# Mach_PLC.net
KiCad netlist of a schematic drawn in Altium Designer
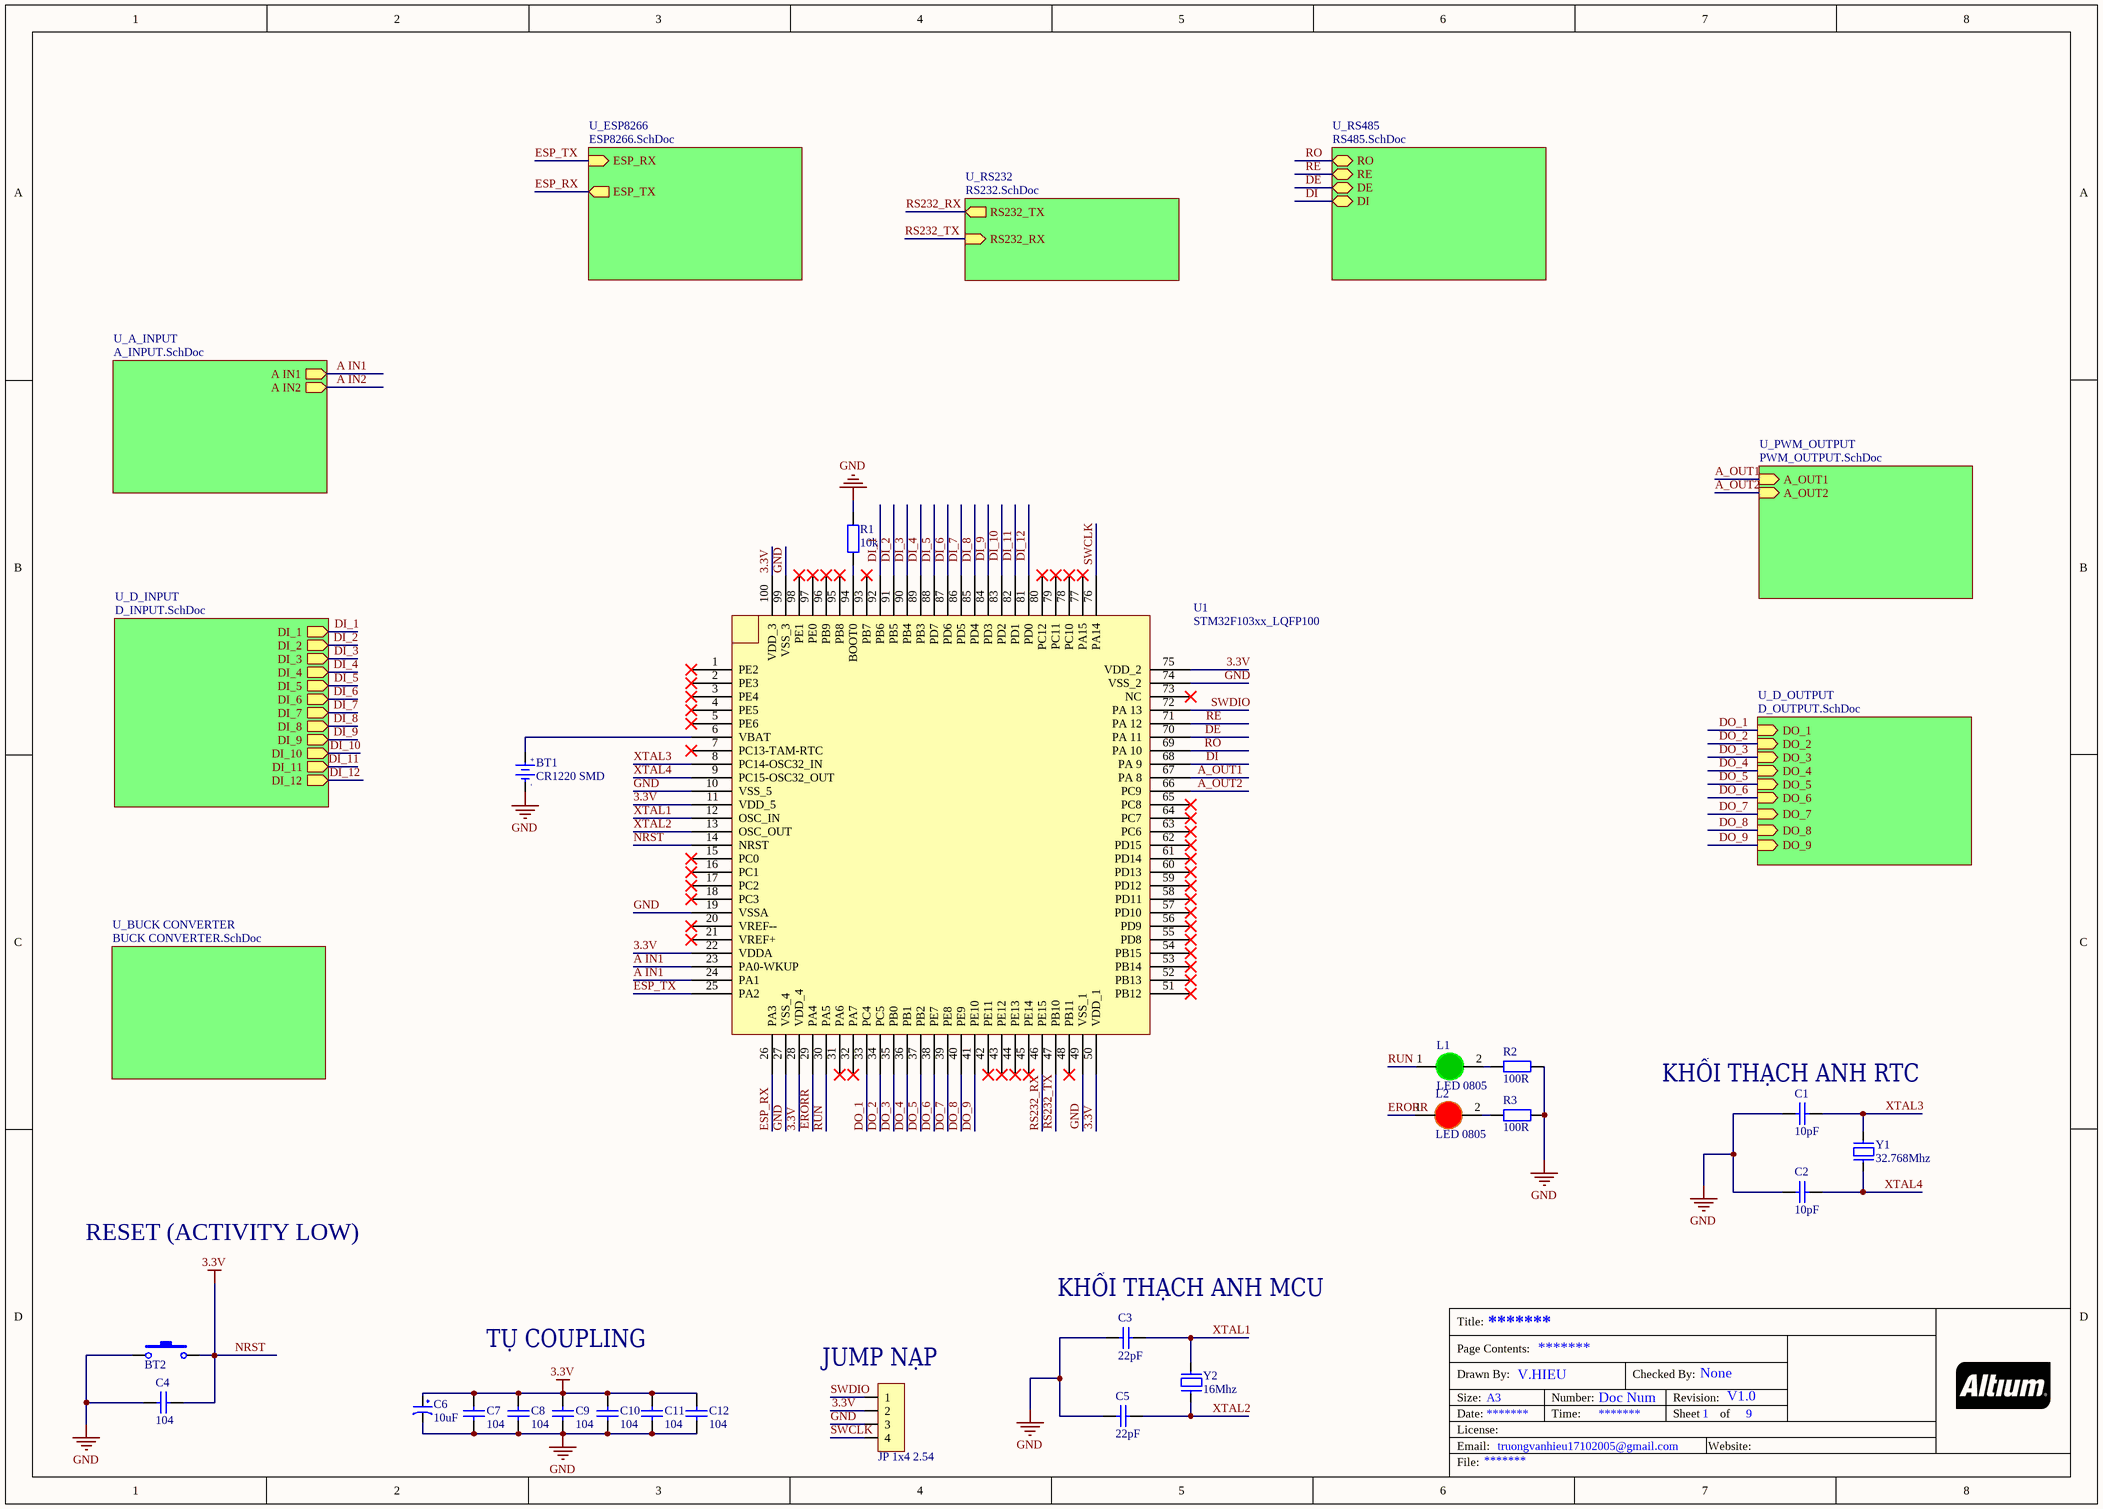
[diagram p0: Mach_PLC.SchDoc]

(export (version "E")
  (design (tool "Eeschema 10.0.6"))
  (components
    (comp (ref "BT1")
      (value "CR1220 SMD")
      (footprint "DE PIN CR1220")
      (libsource (lib "Altium_Lib_by_KhueNguyenCreator") (part "De pin CR1220 SMD"))
    )
    (comp (ref "BT2")
      (value "Nut Nhan 2 Chan SMD 3x6x2.5")
      (footprint "Nut Nhan 2 Chan SMD 3x6x2.5")
      (libsource (lib "Altium_Lib_by_KhueNguyenCreator") (part "Nut Nhan 2 Chan SMD 3x6x2.5"))
    )
    (comp (ref "C1")
      (value "10pF")
      (footprint "tu 0805")
      (description "Dán")
      (libsource (lib "Altium_Lib_by_KhueNguyenCreator") (part "Tu 0805 10pF 50V 10%"))
    )
    (comp (ref "C2")
      (value "10pF")
      (footprint "tu 0805")
      (description "Dán")
      (libsource (lib "Altium_Lib_by_KhueNguyenCreator") (part "Tu 0805 10pF 50V 10%"))
    )
    (comp (ref "C3")
      (value "22pF")
      (footprint "tu 0805")
      (description "Dán")
      (libsource (lib "Altium_Lib_by_KhueNguyenCreator") (part "Tu 0805 22pF 50V 10%"))
    )
    (comp (ref "C4")
      (value "104")
      (footprint "tu 0805")
      (description "Dán")
      (libsource (lib "Altium_Lib_by_KhueNguyenCreator") (part "Tu 0805 104 50V 10%"))
    )
    (comp (ref "C5")
      (value "22pF")
      (footprint "tu 0805")
      (description "Dán")
      (libsource (lib "Altium_Lib_by_KhueNguyenCreator") (part "Tu 0805 22pF 50V 10%"))
    )
    (comp (ref "C6")
      (value "10uF")
      (footprint "tu tantalum smd3216")
      (description "Dán")
      (libsource (lib "Altium_Lib_by_KhueNguyenCreator") (part "Tu tantalum 10uF 16V SMD3216"))
    )
    (comp (ref "C7")
      (value "104")
      (footprint "tu 0805")
      (description "Dán")
      (libsource (lib "Altium_Lib_by_KhueNguyenCreator") (part "Tu 0805 104 50V 10%"))
    )
    (comp (ref "C8")
      (value "104")
      (footprint "tu 0805")
      (description "Dán")
      (libsource (lib "Altium_Lib_by_KhueNguyenCreator") (part "Tu 0805 104 50V 10%"))
    )
    (comp (ref "C9")
      (value "104")
      (footprint "tu 0805")
      (description "Dán")
      (libsource (lib "Altium_Lib_by_KhueNguyenCreator") (part "Tu 0805 104 50V 10%"))
    )
    (comp (ref "C10")
      (value "104")
      (footprint "tu 0805")
      (description "Dán")
      (libsource (lib "Altium_Lib_by_KhueNguyenCreator") (part "Tu 0805 104 50V 10%"))
    )
    (comp (ref "C11")
      (value "104")
      (footprint "tu 0805")
      (description "Dán")
      (libsource (lib "Altium_Lib_by_KhueNguyenCreator") (part "Tu 0805 104 50V 10%"))
    )
    (comp (ref "C12")
      (value "104")
      (footprint "tu 0805")
      (description "Dán")
      (libsource (lib "Altium_Lib_by_KhueNguyenCreator") (part "Tu 0805 104 50V 10%"))
    )
    (comp (ref "JP1")
      (value "JP 1x4 2.54")
      (footprint "JP 1x4 DT")
      (description "Cắm")
      (libsource (lib "Altium_Lib_by_KhueNguyenCreator") (part "JP 1x4 2.54 Duc Thang"))
    )
    (comp (ref "L1")
      (value "LED 0805")
      (footprint "LED-0805-Green")
      (description "Dán")
      (libsource (lib "Altium_Lib_by_KhueNguyenCreator") (part "LED 0805 Xanh La"))
    )
    (comp (ref "L2")
      (value "LED 0805")
      (footprint "LED-0805-Red")
      (description "Dán")
      (libsource (lib "Altium_Lib_by_KhueNguyenCreator") (part "LED 0805 Do"))
    )
    (comp (ref "R1")
      (value "10k")
      (footprint "tro smd 0805")
      (description "Dán")
      (libsource (lib "Altium_Lib_by_KhueNguyenCreator") (part "Tro 0805 1% 10k"))
    )
    (comp (ref "R2")
      (value "100R")
      (footprint "tro smd 0805")
      (description "Dán")
      (libsource (lib "Altium_Lib_by_KhueNguyenCreator") (part "Tro 0805 5% 100R"))
    )
    (comp (ref "R3")
      (value "100R")
      (footprint "tro smd 0805")
      (description "Dán")
      (libsource (lib "Altium_Lib_by_KhueNguyenCreator") (part "Tro 0805 5% 100R"))
    )
    (comp (ref "U1")
      (value "STM32F103xx_LQFP100")
      (footprint "STM32_LQFP100")
      (libsource (lib "Altium_Lib_by_KhueNguyenCreator") (part "STM32F103xx_LQFP100"))
    )
    (comp (ref "Y1")
      (value "32.768Mhz")
      (footprint "Thach Anh 2 Chan 32,768 KHz")
      (description "Crystal For all Crystal 2pin.")
      (libsource (lib "Altium_Lib_by_KhueNguyenCreator") (part "Thach Anh 2 chan 32,768 Khz"))
    )
    (comp (ref "Y2")
      (value "16Mhz")
      (footprint "Thach Anh 2 chan SMD")
      (description "Crystal For all Crystal 2pin.")
      (libsource (lib "Altium_Lib_by_KhueNguyenCreator") (part "Thach Anh 2 chan SMD"))
    )
  )
  (nets
    (net (code "1") (name "/A IN1") (class "Default")
      (node (ref "U1") (pin "23") (pinfunction "PA0-WKUP_23") (pintype "passive"))
      (node (ref "U1") (pin "24") (pinfunction "PA1_24") (pintype "passive"))
    )
    (net (code "3") (name "/A_OUT1") (class "Default")
      (node (ref "U1") (pin "67") (pinfunction "PA_8_67") (pintype "passive"))
    )
    (net (code "4") (name "/A_OUT2") (class "Default")
      (node (ref "U1") (pin "66") (pinfunction "PC9_66") (pintype "passive"))
    )
    (net (code "5") (name "/DE") (class "Default")
      (node (ref "U1") (pin "70") (pinfunction "PA_11_70") (pintype "passive"))
    )
    (net (code "6") (name "/DI") (class "Default")
      (node (ref "U1") (pin "68") (pinfunction "PA_9_68") (pintype "passive"))
    )
    (net (code "7") (name "/DI_1") (class "Default")
      (node (ref "U1") (pin "92") (pinfunction "PB6_92") (pintype "passive"))
    )
    (net (code "8") (name "/DI_2") (class "Default")
      (node (ref "U1") (pin "91") (pinfunction "PB5_91") (pintype "passive"))
    )
    (net (code "9") (name "/DI_3") (class "Default")
      (node (ref "U1") (pin "90") (pinfunction "PB4_90") (pintype "passive"))
    )
    (net (code "10") (name "/DI_4") (class "Default")
      (node (ref "U1") (pin "89") (pinfunction "PB3_89") (pintype "passive"))
    )
    (net (code "11") (name "/DI_5") (class "Default")
      (node (ref "U1") (pin "88") (pinfunction "PD7_88") (pintype "passive"))
    )
    (net (code "12") (name "/DI_6") (class "Default")
      (node (ref "U1") (pin "87") (pinfunction "PD6_87") (pintype "passive"))
    )
    (net (code "13") (name "/DI_7") (class "Default")
      (node (ref "U1") (pin "86") (pinfunction "PD5_86") (pintype "passive"))
    )
    (net (code "14") (name "/DI_8") (class "Default")
      (node (ref "U1") (pin "85") (pinfunction "PD4_85") (pintype "passive"))
    )
    (net (code "15") (name "/DI_9") (class "Default")
      (node (ref "U1") (pin "84") (pinfunction "PD3_84") (pintype "passive"))
    )
    (net (code "16") (name "/DI_10") (class "Default")
      (node (ref "U1") (pin "83") (pinfunction "PD2_83") (pintype "passive"))
    )
    (net (code "17") (name "/DI_11") (class "Default")
      (node (ref "U1") (pin "82") (pinfunction "PD1_82") (pintype "passive"))
    )
    (net (code "18") (name "/DI_12") (class "Default")
      (node (ref "U1") (pin "81") (pinfunction "PD0_81") (pintype "passive"))
    )
    (net (code "19") (name "/DO_1") (class "Default")
      (node (ref "U1") (pin "33") (pinfunction "PC4_33") (pintype "passive"))
    )
    (net (code "20") (name "/DO_2") (class "Default")
      (node (ref "U1") (pin "34") (pinfunction "PC5_34") (pintype "passive"))
    )
    (net (code "21") (name "/DO_3") (class "Default")
      (node (ref "U1") (pin "35") (pinfunction "PB0_35") (pintype "passive"))
    )
    (net (code "22") (name "/DO_4") (class "Default")
      (node (ref "U1") (pin "36") (pinfunction "PB1_36") (pintype "passive"))
    )
    (net (code "23") (name "/DO_5") (class "Default")
      (node (ref "U1") (pin "37") (pinfunction "PB2_37") (pintype "passive"))
    )
    (net (code "24") (name "/DO_6") (class "Default")
      (node (ref "U1") (pin "38") (pinfunction "PE7_38") (pintype "passive"))
    )
    (net (code "25") (name "/DO_7") (class "Default")
      (node (ref "U1") (pin "39") (pinfunction "PE8_39") (pintype "passive"))
    )
    (net (code "26") (name "/DO_8") (class "Default")
      (node (ref "U1") (pin "40") (pinfunction "PE9_40") (pintype "passive"))
    )
    (net (code "27") (name "/DO_9") (class "Default")
      (node (ref "U1") (pin "41") (pinfunction "PE10_41") (pintype "passive"))
    )
    (net (code "28") (name "/ERORR") (class "Default")
      (node (ref "L2") (pin "1") (pinfunction "A_1") (pintype "passive"))
      (node (ref "U1") (pin "29") (pinfunction "PA4_29") (pintype "passive"))
    )
    (net (code "29") (name "/ESP_RX") (class "Default")
      (node (ref "U1") (pin "26") (pinfunction "PA3_26") (pintype "passive"))
    )
    (net (code "30") (name "/ESP_TX") (class "Default")
      (node (ref "U1") (pin "25") (pinfunction "PA2_25") (pintype "passive"))
    )
    (net (code "31") (name "/RE") (class "Default")
      (node (ref "U1") (pin "71") (pinfunction "PA_12_71") (pintype "passive"))
    )
    (net (code "32") (name "/RO") (class "Default")
      (node (ref "U1") (pin "69") (pinfunction "PA_10_69") (pintype "passive"))
    )
    (net (code "33") (name "/RS232_RX") (class "Default")
      (node (ref "U1") (pin "46") (pinfunction "PE15_46") (pintype "passive"))
    )
    (net (code "34") (name "/RS232_TX") (class "Default")
      (node (ref "U1") (pin "47") (pinfunction "PB10_47") (pintype "passive"))
    )
    (net (code "35") (name "/RUN") (class "Default")
      (node (ref "L1") (pin "1") (pinfunction "A_1") (pintype "passive"))
      (node (ref "U1") (pin "30") (pinfunction "PA5_30") (pintype "passive"))
    )
    (net (code "36") (name "/SWCLK") (class "Default")
      (node (ref "JP1") (pin "4") (pinfunction "4_4") (pintype "passive"))
      (node (ref "U1") (pin "76") (pinfunction "PA14_76") (pintype "passive"))
    )
    (net (code "37") (name "/SWDIO") (class "Default")
      (node (ref "JP1") (pin "1") (pinfunction "1_1") (pintype "passive"))
      (node (ref "U1") (pin "72") (pinfunction "PA_13_72") (pintype "passive"))
    )
    (net (code "38") (name "/XTAL1") (class "Default")
      (node (ref "C3") (pin "1") (pinfunction "1_1") (pintype "passive"))
      (node (ref "U1") (pin "12") (pinfunction "OSC_IN_12") (pintype "passive"))
      (node (ref "Y2") (pin "2") (pinfunction "2_2") (pintype "passive"))
    )
    (net (code "39") (name "/XTAL2") (class "Default")
      (node (ref "C5") (pin "1") (pinfunction "1_1") (pintype "passive"))
      (node (ref "U1") (pin "13") (pinfunction "OSC_OUT_13") (pintype "passive"))
      (node (ref "Y2") (pin "1") (pinfunction "1_1") (pintype "passive"))
    )
    (net (code "40") (name "/XTAL3") (class "Default")
      (node (ref "C1") (pin "1") (pinfunction "1_1") (pintype "passive"))
      (node (ref "U1") (pin "8") (pinfunction "PC14-OSC32_IN_8") (pintype "passive"))
      (node (ref "Y1") (pin "2") (pinfunction "2_2") (pintype "passive"))
    )
    (net (code "41") (name "/XTAL4") (class "Default")
      (node (ref "C2") (pin "1") (pinfunction "1_1") (pintype "passive"))
      (node (ref "U1") (pin "9") (pinfunction "PC15-OSC32_OUT_9") (pintype "passive"))
      (node (ref "Y1") (pin "1") (pinfunction "1_1") (pintype "passive"))
    )
    (net (code "42") (name "3.3V") (class "Default")
      (node (ref "BT2") (pin "2") (pinfunction "2_2") (pintype "passive"))
      (node (ref "C10") (pin "1") (pinfunction "1_1") (pintype "passive"))
      (node (ref "C11") (pin "1") (pinfunction "1_1") (pintype "passive"))
      (node (ref "C12") (pin "1") (pinfunction "1_1") (pintype "passive"))
      (node (ref "C4") (pin "2") (pinfunction "2_2") (pintype "passive"))
      (node (ref "C6") (pin "1") (pinfunction "1_1") (pintype "passive"))
      (node (ref "C7") (pin "1") (pinfunction "1_1") (pintype "passive"))
      (node (ref "C8") (pin "1") (pinfunction "1_1") (pintype "passive"))
      (node (ref "C9") (pin "1") (pinfunction "1_1") (pintype "passive"))
      (node (ref "JP1") (pin "2") (pinfunction "2_2") (pintype "passive"))
      (node (ref "U1") (pin "100") (pinfunction "VDD_3_100") (pintype "passive"))
      (node (ref "U1") (pin "11") (pinfunction "VDD_5_11") (pintype "passive"))
      (node (ref "U1") (pin "14") (pinfunction "NRST_14") (pintype "passive"))
      (node (ref "U1") (pin "22") (pinfunction "VDDA_22") (pintype "passive"))
      (node (ref "U1") (pin "28") (pinfunction "VDD_4_28") (pintype "passive"))
      (node (ref "U1") (pin "50") (pinfunction "VDD_1_50") (pintype "passive"))
      (node (ref "U1") (pin "75") (pinfunction "VDD_2_75") (pintype "passive"))
    )
    (net (code "43") (name "GND") (class "Default")
      (node (ref "BT1") (pin "2") (pinfunction "GND_2") (pintype "passive"))
      (node (ref "BT2") (pin "1") (pinfunction "1_1") (pintype "passive"))
      (node (ref "C1") (pin "2") (pinfunction "2_2") (pintype "passive"))
      (node (ref "C10") (pin "2") (pinfunction "2_2") (pintype "passive"))
      (node (ref "C11") (pin "2") (pinfunction "2_2") (pintype "passive"))
      (node (ref "C12") (pin "2") (pinfunction "2_2") (pintype "passive"))
      (node (ref "C2") (pin "2") (pinfunction "2_2") (pintype "passive"))
      (node (ref "C3") (pin "2") (pinfunction "2_2") (pintype "passive"))
      (node (ref "C4") (pin "1") (pinfunction "1_1") (pintype "passive"))
      (node (ref "C5") (pin "2") (pinfunction "2_2") (pintype "passive"))
      (node (ref "C6") (pin "2") (pinfunction "2_2") (pintype "passive"))
      (node (ref "C7") (pin "2") (pinfunction "2_2") (pintype "passive"))
      (node (ref "C8") (pin "2") (pinfunction "2_2") (pintype "passive"))
      (node (ref "C9") (pin "2") (pinfunction "2_2") (pintype "passive"))
      (node (ref "JP1") (pin "3") (pinfunction "3_3") (pintype "passive"))
      (node (ref "R1") (pin "2") (pinfunction "2_2") (pintype "passive"))
      (node (ref "R2") (pin "2") (pinfunction "2_2") (pintype "passive"))
      (node (ref "R3") (pin "2") (pinfunction "2_2") (pintype "passive"))
      (node (ref "U1") (pin "10") (pinfunction "VSS_5_10") (pintype "passive"))
      (node (ref "U1") (pin "19") (pinfunction "VSSA_19") (pintype "passive"))
      (node (ref "U1") (pin "27") (pinfunction "VSS_4_27") (pintype "passive"))
      (node (ref "U1") (pin "49") (pinfunction "VSS_1_49") (pintype "passive"))
      (node (ref "U1") (pin "74") (pinfunction "VSS_2_74") (pintype "passive"))
      (node (ref "U1") (pin "99") (pinfunction "VSS_3_99") (pintype "passive"))
    )
    (net (code "44") (name "Net-(BT1-+3V)") (class "Default")
      (node (ref "BT1") (pin "1") (pinfunction "+3V_1") (pintype "passive"))
      (node (ref "U1") (pin "6") (pinfunction "VBAT_6") (pintype "passive"))
    )
    (net (code "45") (name "Net-(L1-K)") (class "Default")
      (node (ref "L1") (pin "2") (pinfunction "K_2") (pintype "passive"))
      (node (ref "R2") (pin "1") (pinfunction "1_1") (pintype "passive"))
    )
    (net (code "46") (name "Net-(L2-K)") (class "Default")
      (node (ref "L2") (pin "2") (pinfunction "K_2") (pintype "passive"))
      (node (ref "R3") (pin "1") (pinfunction "1_1") (pintype "passive"))
    )
    (net (code "47") (name "Net-(U1-BOOT0)") (class "Default")
      (node (ref "R1") (pin "1") (pinfunction "1_1") (pintype "passive"))
      (node (ref "U1") (pin "94") (pinfunction "BOOT0_94") (pintype "passive"))
    )
    (net (code "48") (name "unconnected-(U1-NC-Pad73)") (class "Default")
      (node (ref "U1") (pin "73") (pinfunction "NC_73") (pintype "passive+no_connect"))
    )
    (net (code "49") (name "unconnected-(U1-PA6-Pad31)") (class "Default")
      (node (ref "U1") (pin "31") (pinfunction "PA6_31") (pintype "passive+no_connect"))
    )
    (net (code "50") (name "unconnected-(U1-PA7-Pad32)") (class "Default")
      (node (ref "U1") (pin "32") (pinfunction "PA7_32") (pintype "passive+no_connect"))
    )
    (net (code "51") (name "unconnected-(U1-PA15-Pad77)") (class "Default")
      (node (ref "U1") (pin "77") (pinfunction "PA15_77") (pintype "passive+no_connect"))
    )
    (net (code "52") (name "unconnected-(U1-PB7-Pad93)") (class "Default")
      (node (ref "U1") (pin "93") (pinfunction "PB7_93") (pintype "passive+no_connect"))
    )
    (net (code "53") (name "unconnected-(U1-PB8-Pad95)") (class "Default")
      (node (ref "U1") (pin "95") (pinfunction "PB8_95") (pintype "passive+no_connect"))
    )
    (net (code "54") (name "unconnected-(U1-PB9-Pad96)") (class "Default")
      (node (ref "U1") (pin "96") (pinfunction "PB9_96") (pintype "passive+no_connect"))
    )
    (net (code "55") (name "unconnected-(U1-PB11-Pad48)") (class "Default")
      (node (ref "U1") (pin "48") (pinfunction "PB11_48") (pintype "passive+no_connect"))
    )
    (net (code "56") (name "unconnected-(U1-PB12-Pad51)") (class "Default")
      (node (ref "U1") (pin "51") (pinfunction "PB12_51") (pintype "passive+no_connect"))
    )
    (net (code "57") (name "unconnected-(U1-PB13-Pad52)") (class "Default")
      (node (ref "U1") (pin "52") (pinfunction "PB13_52") (pintype "passive+no_connect"))
    )
    (net (code "58") (name "unconnected-(U1-PB14-Pad53)") (class "Default")
      (node (ref "U1") (pin "53") (pinfunction "PB14_53") (pintype "passive+no_connect"))
    )
    (net (code "59") (name "unconnected-(U1-PB15-Pad54)") (class "Default")
      (node (ref "U1") (pin "54") (pinfunction "PB15_54") (pintype "passive+no_connect"))
    )
    (net (code "60") (name "unconnected-(U1-PC0-Pad15)") (class "Default")
      (node (ref "U1") (pin "15") (pinfunction "PC0_15") (pintype "passive+no_connect"))
    )
    (net (code "61") (name "unconnected-(U1-PC1-Pad16)") (class "Default")
      (node (ref "U1") (pin "16") (pinfunction "PC1_16") (pintype "passive+no_connect"))
    )
    (net (code "62") (name "unconnected-(U1-PC2-Pad17)") (class "Default")
      (node (ref "U1") (pin "17") (pinfunction "PC2_17") (pintype "passive+no_connect"))
    )
    (net (code "63") (name "unconnected-(U1-PC3-Pad18)") (class "Default")
      (node (ref "U1") (pin "18") (pinfunction "PC3_18") (pintype "passive+no_connect"))
    )
    (net (code "64") (name "unconnected-(U1-PC6-Pad63)") (class "Default")
      (node (ref "U1") (pin "63") (pinfunction "PC6_63") (pintype "passive+no_connect"))
    )
    (net (code "65") (name "unconnected-(U1-PC7-Pad64)") (class "Default")
      (node (ref "U1") (pin "64") (pinfunction "PC7_64") (pintype "passive+no_connect"))
    )
    (net (code "66") (name "unconnected-(U1-PC8-Pad65)") (class "Default")
      (node (ref "U1") (pin "65") (pinfunction "PC8_65") (pintype "passive+no_connect"))
    )
    (net (code "67") (name "unconnected-(U1-PC10-Pad78)") (class "Default")
      (node (ref "U1") (pin "78") (pinfunction "PC10_78") (pintype "passive+no_connect"))
    )
    (net (code "68") (name "unconnected-(U1-PC11-Pad79)") (class "Default")
      (node (ref "U1") (pin "79") (pinfunction "PC11_79") (pintype "passive+no_connect"))
    )
    (net (code "69") (name "unconnected-(U1-PC12-Pad80)") (class "Default")
      (node (ref "U1") (pin "80") (pinfunction "PC12_80") (pintype "passive+no_connect"))
    )
    (net (code "70") (name "unconnected-(U1-PC13-TAM-RTC-Pad7)") (class "Default")
      (node (ref "U1") (pin "7") (pinfunction "PC13-TAM-RTC_7") (pintype "passive+no_connect"))
    )
    (net (code "71") (name "unconnected-(U1-PD8-Pad55)") (class "Default")
      (node (ref "U1") (pin "55") (pinfunction "PD8_55") (pintype "passive+no_connect"))
    )
    (net (code "72") (name "unconnected-(U1-PD9-Pad56)") (class "Default")
      (node (ref "U1") (pin "56") (pinfunction "PD9_56") (pintype "passive+no_connect"))
    )
    (net (code "73") (name "unconnected-(U1-PD10-Pad57)") (class "Default")
      (node (ref "U1") (pin "57") (pinfunction "PD10_57") (pintype "passive+no_connect"))
    )
    (net (code "74") (name "unconnected-(U1-PD11-Pad58)") (class "Default")
      (node (ref "U1") (pin "58") (pinfunction "PD11_58") (pintype "passive+no_connect"))
    )
    (net (code "75") (name "unconnected-(U1-PD12-Pad59)") (class "Default")
      (node (ref "U1") (pin "59") (pinfunction "PD12_59") (pintype "passive+no_connect"))
    )
    (net (code "76") (name "unconnected-(U1-PD13-Pad60)") (class "Default")
      (node (ref "U1") (pin "60") (pinfunction "PD13_60") (pintype "passive+no_connect"))
    )
    (net (code "77") (name "unconnected-(U1-PD14-Pad61)") (class "Default")
      (node (ref "U1") (pin "61") (pinfunction "PD14_61") (pintype "passive+no_connect"))
    )
    (net (code "78") (name "unconnected-(U1-PD15-Pad62)") (class "Default")
      (node (ref "U1") (pin "62") (pinfunction "PD15_62") (pintype "passive+no_connect"))
    )
    (net (code "79") (name "unconnected-(U1-PE0-Pad97)") (class "Default")
      (node (ref "U1") (pin "97") (pinfunction "PE0_97") (pintype "passive+no_connect"))
    )
    (net (code "80") (name "unconnected-(U1-PE1-Pad98)") (class "Default")
      (node (ref "U1") (pin "98") (pinfunction "PE1_98") (pintype "passive+no_connect"))
    )
    (net (code "81") (name "unconnected-(U1-PE2-Pad1)") (class "Default")
      (node (ref "U1") (pin "1") (pinfunction "PE2_1") (pintype "passive+no_connect"))
    )
    (net (code "82") (name "unconnected-(U1-PE3-Pad2)") (class "Default")
      (node (ref "U1") (pin "2") (pinfunction "PE3_2") (pintype "passive+no_connect"))
    )
    (net (code "83") (name "unconnected-(U1-PE4-Pad3)") (class "Default")
      (node (ref "U1") (pin "3") (pinfunction "PE4_3") (pintype "passive+no_connect"))
    )
    (net (code "84") (name "unconnected-(U1-PE5-Pad4)") (class "Default")
      (node (ref "U1") (pin "4") (pinfunction "PE5_4") (pintype "passive+no_connect"))
    )
    (net (code "85") (name "unconnected-(U1-PE6-Pad5)") (class "Default")
      (node (ref "U1") (pin "5") (pinfunction "PE6_5") (pintype "passive+no_connect"))
    )
    (net (code "86") (name "unconnected-(U1-PE11-Pad42)") (class "Default")
      (node (ref "U1") (pin "42") (pinfunction "PE11_42") (pintype "passive+no_connect"))
    )
    (net (code "87") (name "unconnected-(U1-PE12-Pad43)") (class "Default")
      (node (ref "U1") (pin "43") (pinfunction "PE12_43") (pintype "passive+no_connect"))
    )
    (net (code "88") (name "unconnected-(U1-PE13-Pad44)") (class "Default")
      (node (ref "U1") (pin "44") (pinfunction "PE13_44") (pintype "passive+no_connect"))
    )
    (net (code "89") (name "unconnected-(U1-PE14-Pad45)") (class "Default")
      (node (ref "U1") (pin "45") (pinfunction "PE14_45") (pintype "passive+no_connect"))
    )
    (net (code "90") (name "unconnected-(U1-VREF+-Pad21)") (class "Default")
      (node (ref "U1") (pin "21") (pinfunction "VREF+_21") (pintype "passive+no_connect"))
    )
    (net (code "91") (name "unconnected-(U1-VREF---Pad20)") (class "Default")
      (node (ref "U1") (pin "20") (pinfunction "VREF--_20") (pintype "passive+no_connect"))
    )
  )
)
